# nrfModule.net
KiCad netlist of a schematic drawn in EAGLE
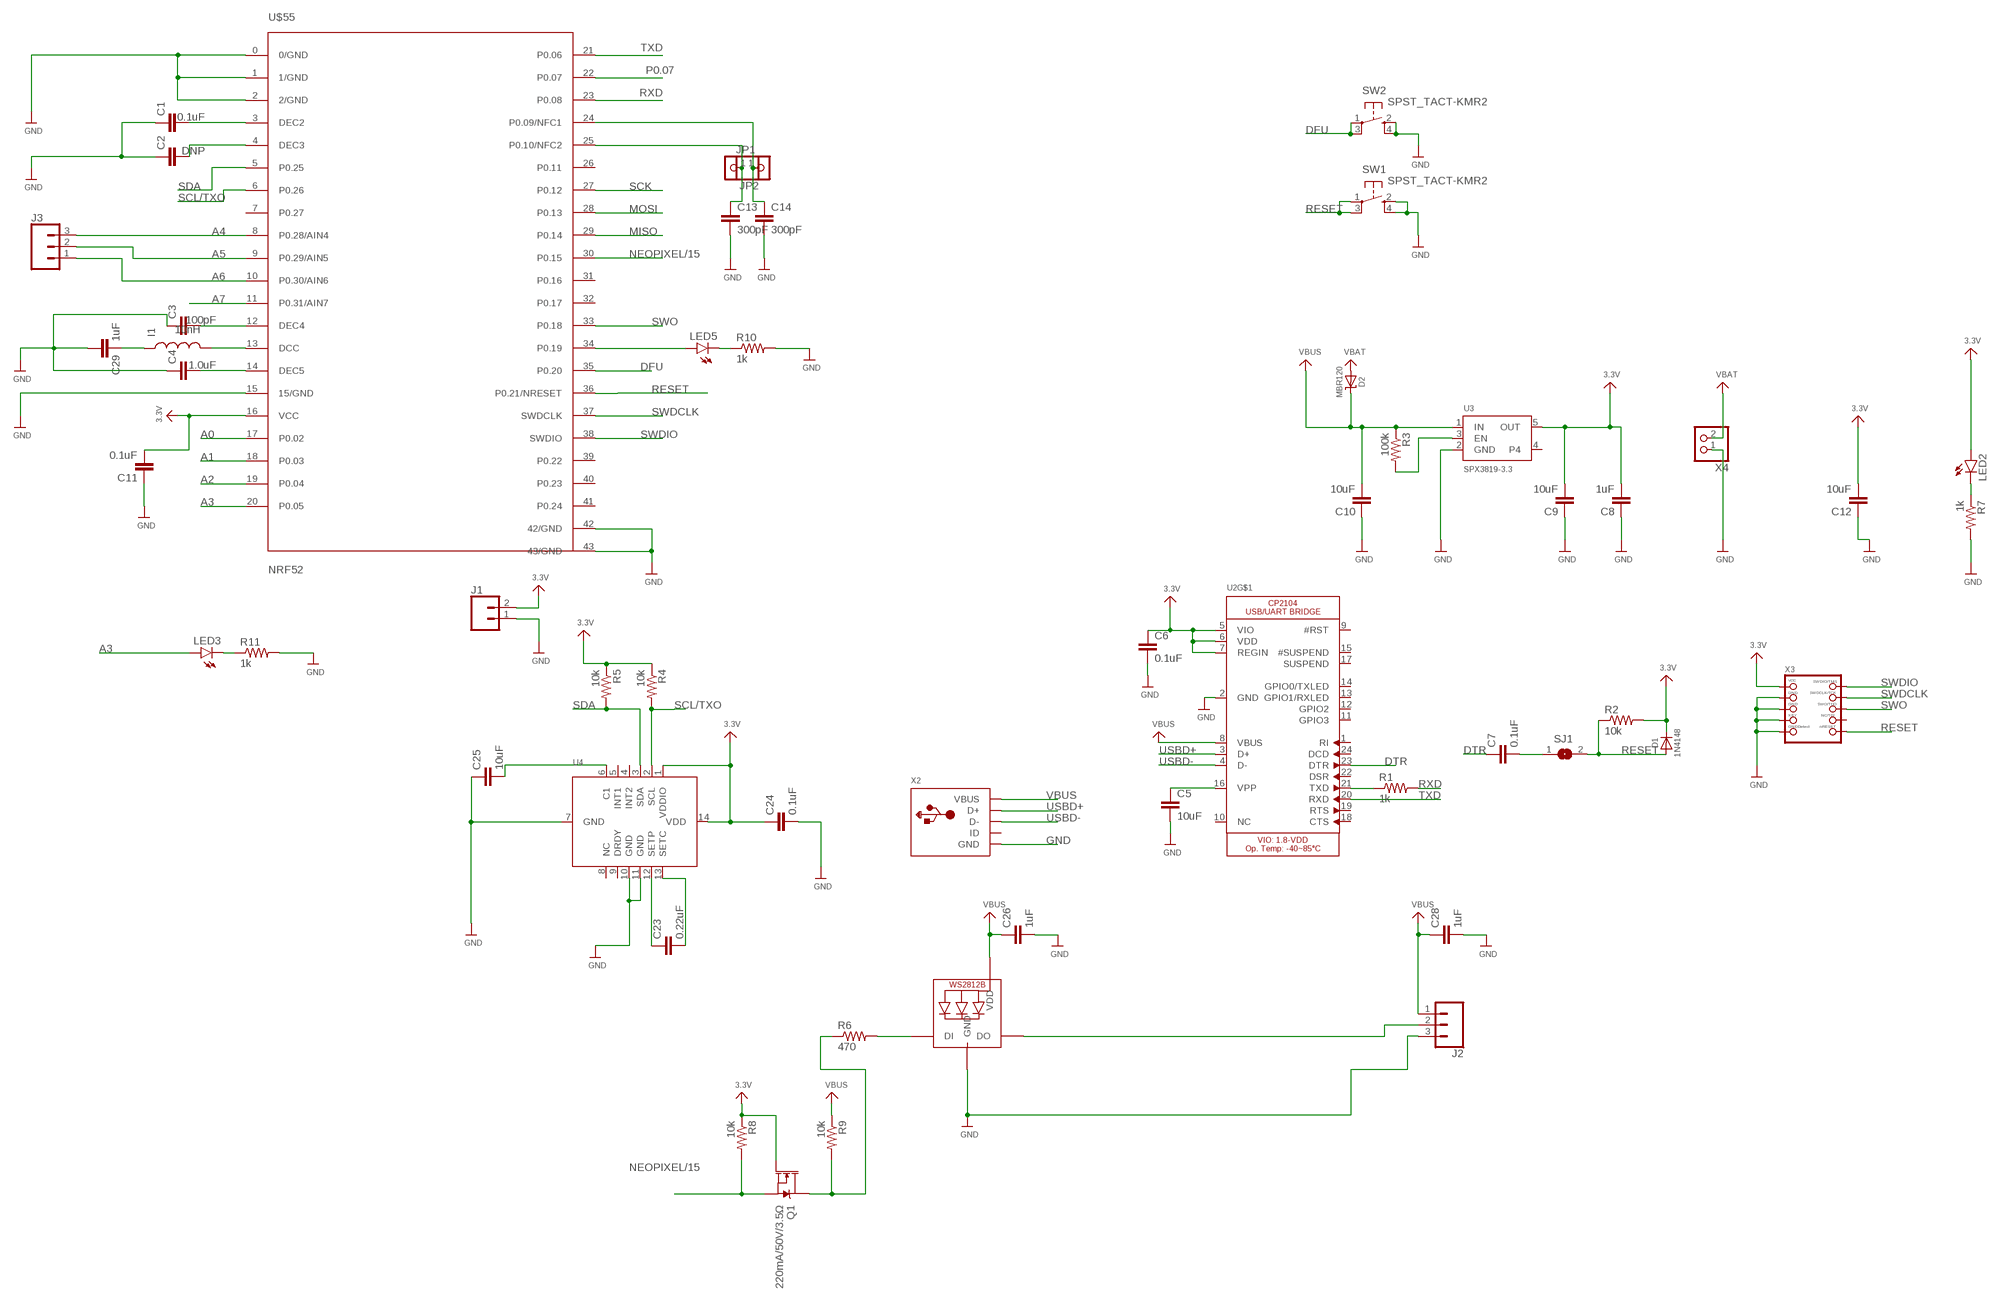
[diagram p0: schematic, sheet 1]

(export (version "E")
  (design (tool "Eeschema 10.0.6"))
  (components
    (comp (ref "C1")
      (value "0.1uF")
      (footprint "eagle-import:0805")
      (libsource (lib "eagle-import") (part "CAP"))
    )
    (comp (ref "C2")
      (value "DNP")
      (footprint "eagle-import:0805")
      (libsource (lib "eagle-import") (part "CAP"))
    )
    (comp (ref "C3")
      (value "100pF")
      (footprint "eagle-import:0805")
      (libsource (lib "eagle-import") (part "CAP"))
    )
    (comp (ref "C4")
      (value "1.0uF")
      (footprint "eagle-import:0805")
      (libsource (lib "eagle-import") (part "CAP"))
    )
    (comp (ref "C5")
      (value "10uF")
      (footprint "eagle-import:0805")
      (libsource (lib "eagle-import") (part "CAP"))
    )
    (comp (ref "C6")
      (value "0.1uF")
      (footprint "eagle-import:0805")
      (libsource (lib "eagle-import") (part "CAP"))
    )
    (comp (ref "C7")
      (value "0.1uF")
      (footprint "eagle-import:0805")
      (libsource (lib "eagle-import") (part "CAP"))
    )
    (comp (ref "C8")
      (value "1uF")
      (footprint "eagle-import:0805")
      (libsource (lib "eagle-import") (part "CAP"))
    )
    (comp (ref "C9")
      (value "10uF")
      (footprint "eagle-import:0805")
      (libsource (lib "eagle-import") (part "CAP"))
    )
    (comp (ref "C10")
      (value "10uF")
      (footprint "eagle-import:0805")
      (libsource (lib "eagle-import") (part "CAP"))
    )
    (comp (ref "C11")
      (value "0.1uF")
      (footprint "eagle-import:0805")
      (libsource (lib "eagle-import") (part "CAP"))
    )
    (comp (ref "C12")
      (value "10uF")
      (footprint "eagle-import:0805")
      (libsource (lib "eagle-import") (part "CAP"))
    )
    (comp (ref "C13")
      (value "300pF")
      (footprint "eagle-import:0805")
      (libsource (lib "eagle-import") (part "CAP"))
    )
    (comp (ref "C14")
      (value "300pF")
      (footprint "eagle-import:0805")
      (libsource (lib "eagle-import") (part "CAP"))
    )
    (comp (ref "C23")
      (value "0.22uF")
      (footprint "eagle-import:0805")
      (libsource (lib "eagle-import") (part "CAP"))
    )
    (comp (ref "C24")
      (value "0.1uF")
      (footprint "eagle-import:0805")
      (libsource (lib "eagle-import") (part "CAP"))
    )
    (comp (ref "C25")
      (value "10uF")
      (footprint "eagle-import:0805")
      (libsource (lib "eagle-import") (part "CAP"))
    )
    (comp (ref "C26")
      (value "1uF")
      (footprint "eagle-import:0805")
      (libsource (lib "eagle-import") (part "CAP"))
    )
    (comp (ref "C28")
      (value "1uF")
      (footprint "eagle-import:0805")
      (libsource (lib "eagle-import") (part "CAP"))
    )
    (comp (ref "C29")
      (value "1uF")
      (footprint "eagle-import:0805")
      (libsource (lib "eagle-import") (part "CAP"))
    )
    (comp (ref "D1")
      (value "1N4148")
      (footprint "eagle-import:SOD-323")
      (libsource (lib "eagle-import") (part "DIODESOD-323"))
    )
    (comp (ref "D2")
      (value "MBR120")
      (footprint "eagle-import:SOD-123")
      (libsource (lib "eagle-import") (part "DIODE-SCHOTTKYSOD-123"))
    )
    (comp (ref "I1")
      (value "10nH")
      (footprint "eagle-import:0805")
      (libsource (lib "eagle-import") (part "IND"))
    )
    (comp (ref "J1")
      (value "CONN_02")
      (footprint "eagle-import:1X02")
      (libsource (lib "eagle-import") (part "CONN_02"))
    )
    (comp (ref "J2")
      (value "CONN_03")
      (footprint "eagle-import:1X03")
      (libsource (lib "eagle-import") (part "CONN_03"))
    )
    (comp (ref "J3")
      (value "CONN_03")
      (footprint "eagle-import:1X03")
      (libsource (lib "eagle-import") (part "CONN_03"))
    )
    (comp (ref "JP1")
      (value "HEADER-1X12MM")
      (footprint "eagle-import:1X01_2MM")
      (libsource (lib "eagle-import") (part "HEADER-1X12MM"))
    )
    (comp (ref "JP2")
      (value "HEADER-1X12MM")
      (footprint "eagle-import:1X01_2MM")
      (libsource (lib "eagle-import") (part "HEADER-1X12MM"))
    )
    (comp (ref "LED1")
      (value "WS2812B5050")
      (footprint "eagle-import:WS2812B")
      (libsource (lib "eagle-import") (part "WS2812B5050"))
    )
    (comp (ref "LED2")
      (value "LED0603")
      (footprint "eagle-import:LED-0603")
      (libsource (lib "eagle-import") (part "LED0603"))
    )
    (comp (ref "LED3")
      (value "LED0603")
      (footprint "eagle-import:LED-0603")
      (libsource (lib "eagle-import") (part "LED0603"))
    )
    (comp (ref "LED5")
      (value "LED0603")
      (footprint "eagle-import:LED-0603")
      (libsource (lib "eagle-import") (part "LED0603"))
    )
    (comp (ref "Q1")
      (value "220mA/50V/3.5Ω")
      (footprint "eagle-import:SOT23-3")
      (libsource (lib "eagle-import") (part "MOSFET-NCH-BSS138"))
    )
    (comp (ref "R1")
      (value "1k")
      (footprint "eagle-import:0805")
      (libsource (lib "eagle-import") (part "RES"))
    )
    (comp (ref "R2")
      (value "10k")
      (footprint "eagle-import:0805")
      (libsource (lib "eagle-import") (part "RES"))
    )
    (comp (ref "R3")
      (value "100k")
      (footprint "eagle-import:0805")
      (libsource (lib "eagle-import") (part "RES"))
    )
    (comp (ref "R4")
      (value "10k")
      (footprint "eagle-import:0805")
      (libsource (lib "eagle-import") (part "RES"))
    )
    (comp (ref "R5")
      (value "10k")
      (footprint "eagle-import:0805")
      (libsource (lib "eagle-import") (part "RES"))
    )
    (comp (ref "R6")
      (value "470")
      (footprint "eagle-import:0805")
      (libsource (lib "eagle-import") (part "RES"))
    )
    (comp (ref "R7")
      (value "1k")
      (footprint "eagle-import:0805")
      (libsource (lib "eagle-import") (part "RES"))
    )
    (comp (ref "R8")
      (value "10k")
      (footprint "eagle-import:0805")
      (libsource (lib "eagle-import") (part "RES"))
    )
    (comp (ref "R9")
      (value "10k")
      (footprint "eagle-import:0805")
      (libsource (lib "eagle-import") (part "RES"))
    )
    (comp (ref "R10")
      (value "1k")
      (footprint "eagle-import:0805")
      (libsource (lib "eagle-import") (part "RES"))
    )
    (comp (ref "R11")
      (value "1k")
      (footprint "eagle-import:0805")
      (libsource (lib "eagle-import") (part "RES"))
    )
    (comp (ref "SJ1")
      (value "SOLDERJUMPERCLOSED")
      (footprint "eagle-import:SOLDERJUMPER_CLOSEDWIRE")
      (libsource (lib "eagle-import") (part "SOLDERJUMPERCLOSED"))
    )
    (comp (ref "SW1")
      (value "SPST_TACT-KMR2")
      (footprint "eagle-import:KMR2")
      (libsource (lib "eagle-import") (part "SPST_TACT-KMR2"))
    )
    (comp (ref "SW2")
      (value "SPST_TACT-KMR2")
      (footprint "eagle-import:KMR2")
      (libsource (lib "eagle-import") (part "SPST_TACT-KMR2"))
    )
    (comp (ref "U$55")
      (value "NRF52")
      (footprint "eagle-import:NRF52")
      (libsource (lib "eagle-import") (part "NRF52"))
    )
    (comp (ref "U2")
      (value "CP2104")
      (footprint "eagle-import:QFN24_4MM_SMSC")
      (libsource (lib "eagle-import") (part "CP2104"))
    )
    (comp (ref "U3")
      (value "SPX3819-3.3")
      (footprint "eagle-import:SOT23-5")
      (libsource (lib "eagle-import") (part "VREG_SOT23-5"))
    )
    (comp (ref "U4")
      (value "LSM303DLHC")
      (footprint "eagle-import:LGA14")
      (libsource (lib "eagle-import") (part "LSM303DLHC"))
    )
    (comp (ref "X2")
      (value "USB_MICRO_20329_V2")
      (footprint "eagle-import:4UCONN_20329_V2")
      (libsource (lib "eagle-import") (part "USB_MICRO_20329_V2"))
    )
    (comp (ref "X3")
      (value "JTAG-CORTEX")
      (footprint "eagle-import:2X05_1.27MM_SMT")
      (libsource (lib "eagle-import") (part "JTAG-CORTEX"))
    )
    (comp (ref "X4")
      (value "CON_JST_PH_2PIN")
      (footprint "eagle-import:JSTPH2")
      (libsource (lib "eagle-import") (part "CON_JST_PH_2PIN"))
    )
  )
  (nets
    (net (code "1") (name "/A0") (class "Default")
      (node (ref "U$55") (pin "17") (pinfunction "P0.02_17") (pintype "bidirectional"))
    )
    (net (code "2") (name "/A1") (class "Default")
      (node (ref "U$55") (pin "18") (pinfunction "P0.03_18") (pintype "bidirectional"))
    )
    (net (code "3") (name "/A2") (class "Default")
      (node (ref "U$55") (pin "19") (pinfunction "P0.04_19") (pintype "bidirectional"))
    )
    (net (code "4") (name "/A3") (class "Default")
      (node (ref "LED3") (pin "A") (pinfunction "A_A") (pintype "passive"))
      (node (ref "U$55") (pin "20") (pinfunction "P0.05_20") (pintype "bidirectional"))
    )
    (net (code "5") (name "/A4") (class "Default")
      (node (ref "J3") (pin "3") (pinfunction "3_3") (pintype "passive"))
      (node (ref "U$55") (pin "8") (pinfunction "P0.28/AIN4_8") (pintype "bidirectional"))
    )
    (net (code "6") (name "/A5") (class "Default")
      (node (ref "J3") (pin "2") (pinfunction "2_2") (pintype "passive"))
      (node (ref "U$55") (pin "9") (pinfunction "P0.29/AIN5_9") (pintype "bidirectional"))
    )
    (net (code "7") (name "/A6") (class "Default")
      (node (ref "J3") (pin "1") (pinfunction "1_1") (pintype "passive"))
      (node (ref "U$55") (pin "10") (pinfunction "P0.30/AIN6_10") (pintype "bidirectional"))
    )
    (net (code "8") (name "/A7") (class "Default")
      (node (ref "U$55") (pin "11") (pinfunction "P0.31/AIN7_11") (pintype "bidirectional"))
    )
    (net (code "9") (name "/DFU") (class "Default")
      (node (ref "SW2") (pin "1") (pinfunction "P_1") (pintype "passive"))
      (node (ref "SW2") (pin "3") (pinfunction "P1_3") (pintype "passive"))
      (node (ref "U$55") (pin "35") (pinfunction "P0.20_35") (pintype "bidirectional"))
    )
    (net (code "10") (name "/DTR") (class "Default")
      (node (ref "C7") (pin "1") (pinfunction "1_1") (pintype "passive"))
      (node (ref "U2") (pin "23") (pinfunction "DTR_23") (pintype "output"))
    )
    (net (code "11") (name "/MISO") (class "Default")
      (node (ref "U$55") (pin "29") (pinfunction "P0.14_29") (pintype "bidirectional"))
    )
    (net (code "12") (name "/MOSI") (class "Default")
      (node (ref "U$55") (pin "28") (pinfunction "P0.13_28") (pintype "bidirectional"))
    )
    (net (code "13") (name "/NEOPIXEL{slash}15") (class "Default")
      (node (ref "Q1") (pin "2") (pinfunction "S_2") (pintype "bidirectional"))
      (node (ref "R8") (pin "2") (pinfunction "2_2") (pintype "passive"))
      (node (ref "U$55") (pin "30") (pinfunction "P0.15_30") (pintype "bidirectional"))
    )
    (net (code "14") (name "/P0.07") (class "Default")
      (node (ref "U$55") (pin "22") (pinfunction "P0.07_22") (pintype "bidirectional"))
    )
    (net (code "15") (name "/RESET") (class "Default")
      (node (ref "D1") (pin "A") (pinfunction "A_A") (pintype "passive"))
      (node (ref "R2") (pin "1") (pinfunction "1_1") (pintype "passive"))
      (node (ref "SJ1") (pin "2") (pinfunction "2_2") (pintype "passive"))
      (node (ref "SW1") (pin "1") (pinfunction "P_1") (pintype "passive"))
      (node (ref "SW1") (pin "3") (pinfunction "P1_3") (pintype "passive"))
      (node (ref "U$55") (pin "36") (pinfunction "P0.21/NRESET_36") (pintype "bidirectional"))
      (node (ref "X3") (pin "10") (pinfunction "NRESET_10") (pintype "bidirectional"))
    )
    (net (code "16") (name "/RXD") (class "Default")
      (node (ref "R1") (pin "2") (pinfunction "2_2") (pintype "passive"))
      (node (ref "U$55") (pin "23") (pinfunction "P0.08_23") (pintype "bidirectional"))
    )
    (net (code "17") (name "/SCK") (class "Default")
      (node (ref "U$55") (pin "27") (pinfunction "P0.12_27") (pintype "bidirectional"))
    )
    (net (code "18") (name "/SCL{slash}TXO") (class "Default")
      (node (ref "R4") (pin "2") (pinfunction "2_2") (pintype "passive"))
      (node (ref "U$55") (pin "6") (pinfunction "P0.26_6") (pintype "bidirectional"))
      (node (ref "U4") (pin "2") (pinfunction "SCL_2") (pintype "bidirectional"))
    )
    (net (code "19") (name "/SDA") (class "Default")
      (node (ref "R5") (pin "2") (pinfunction "2_2") (pintype "passive"))
      (node (ref "U$55") (pin "5") (pinfunction "P0.25_5") (pintype "bidirectional"))
      (node (ref "U4") (pin "3") (pinfunction "SDA_3") (pintype "bidirectional"))
    )
    (net (code "20") (name "/SWDCLK") (class "Default")
      (node (ref "U$55") (pin "37") (pinfunction "SWDCLK_37") (pintype "bidirectional"))
      (node (ref "X3") (pin "4") (pinfunction "SWDCLK_4") (pintype "bidirectional"))
    )
    (net (code "21") (name "/SWDIO") (class "Default")
      (node (ref "U$55") (pin "38") (pinfunction "SWDIO_38") (pintype "bidirectional"))
      (node (ref "X3") (pin "2") (pinfunction "SWDIO_2") (pintype "bidirectional"))
    )
    (net (code "22") (name "/SWO") (class "Default")
      (node (ref "U$55") (pin "33") (pinfunction "P0.18_33") (pintype "bidirectional"))
      (node (ref "X3") (pin "6") (pinfunction "SWO_6") (pintype "bidirectional"))
    )
    (net (code "23") (name "/TXD") (class "Default")
      (node (ref "U$55") (pin "21") (pinfunction "P0.06_21") (pintype "bidirectional"))
      (node (ref "U2") (pin "20") (pinfunction "RXD_20") (pintype "input"))
    )
    (net (code "24") (name "/USBD+") (class "Default")
      (node (ref "U2") (pin "3") (pinfunction "D+_3") (pintype "bidirectional"))
      (node (ref "X2") (pin "D+") (pinfunction "D+_D+") (pintype "bidirectional"))
    )
    (net (code "25") (name "/USBD-") (class "Default")
      (node (ref "U2") (pin "4") (pinfunction "D-_4") (pintype "bidirectional"))
      (node (ref "X2") (pin "D-") (pinfunction "D-_D-") (pintype "bidirectional"))
    )
    (net (code "26") (name "3.3V") (class "Default")
      (node (ref "C11") (pin "2") (pinfunction "2_2") (pintype "passive"))
      (node (ref "C12") (pin "2") (pinfunction "2_2") (pintype "passive"))
      (node (ref "C24") (pin "1") (pinfunction "1_1") (pintype "passive"))
      (node (ref "C6") (pin "1") (pinfunction "1_1") (pintype "passive"))
      (node (ref "C8") (pin "2") (pinfunction "2_2") (pintype "passive"))
      (node (ref "C9") (pin "2") (pinfunction "2_2") (pintype "passive"))
      (node (ref "D1") (pin "C") (pinfunction "C_C") (pintype "passive"))
      (node (ref "J1") (pin "2") (pinfunction "2_2") (pintype "passive"))
      (node (ref "LED2") (pin "A") (pinfunction "A_A") (pintype "passive"))
      (node (ref "Q1") (pin "1") (pinfunction "G_1") (pintype "bidirectional"))
      (node (ref "R2") (pin "2") (pinfunction "2_2") (pintype "passive"))
      (node (ref "R4") (pin "1") (pinfunction "1_1") (pintype "passive"))
      (node (ref "R5") (pin "1") (pinfunction "1_1") (pintype "passive"))
      (node (ref "R8") (pin "1") (pinfunction "1_1") (pintype "passive"))
      (node (ref "U$55") (pin "16") (pinfunction "VCC_16") (pintype "bidirectional"))
      (node (ref "U2") (pin "5") (pinfunction "VIO_5") (pintype "power_in"))
      (node (ref "U2") (pin "6") (pinfunction "VDD_6") (pintype "power_in"))
      (node (ref "U2") (pin "7") (pinfunction "REGIN_7") (pintype "power_in"))
      (node (ref "U3") (pin "5") (pinfunction "OUT_5") (pintype "power_in"))
      (node (ref "U4") (pin "1") (pinfunction "VDDIO_1") (pintype "power_in"))
      (node (ref "U4") (pin "14") (pinfunction "VDD_14") (pintype "power_in"))
      (node (ref "X3") (pin "1") (pinfunction "VCC_1") (pintype "power_in"))
    )
    (net (code "27") (name "GND") (class "Default")
      (node (ref "C1") (pin "1") (pinfunction "1_1") (pintype "passive"))
      (node (ref "C10") (pin "1") (pinfunction "1_1") (pintype "passive"))
      (node (ref "C11") (pin "1") (pinfunction "1_1") (pintype "passive"))
      (node (ref "C12") (pin "1") (pinfunction "1_1") (pintype "passive"))
      (node (ref "C13") (pin "2") (pinfunction "2_2") (pintype "passive"))
      (node (ref "C14") (pin "2") (pinfunction "2_2") (pintype "passive"))
      (node (ref "C2") (pin "1") (pinfunction "1_1") (pintype "passive"))
      (node (ref "C24") (pin "2") (pinfunction "2_2") (pintype "passive"))
      (node (ref "C25") (pin "1") (pinfunction "1_1") (pintype "passive"))
      (node (ref "C26") (pin "2") (pinfunction "2_2") (pintype "passive"))
      (node (ref "C28") (pin "2") (pinfunction "2_2") (pintype "passive"))
      (node (ref "C29") (pin "2") (pinfunction "2_2") (pintype "passive"))
      (node (ref "C3") (pin "1") (pinfunction "1_1") (pintype "passive"))
      (node (ref "C4") (pin "1") (pinfunction "1_1") (pintype "passive"))
      (node (ref "C5") (pin "2") (pinfunction "2_2") (pintype "passive"))
      (node (ref "C6") (pin "2") (pinfunction "2_2") (pintype "passive"))
      (node (ref "C8") (pin "1") (pinfunction "1_1") (pintype "passive"))
      (node (ref "C9") (pin "1") (pinfunction "1_1") (pintype "passive"))
      (node (ref "J1") (pin "1") (pinfunction "1_1") (pintype "passive"))
      (node (ref "J2") (pin "3") (pinfunction "3_3") (pintype "passive"))
      (node (ref "LED1") (pin "3-GND") (pinfunction "GND_3-GND") (pintype "power_in"))
      (node (ref "R10") (pin "2") (pinfunction "2_2") (pintype "passive"))
      (node (ref "R11") (pin "2") (pinfunction "2_2") (pintype "passive"))
      (node (ref "R7") (pin "2") (pinfunction "2_2") (pintype "passive"))
      (node (ref "SW1") (pin "2") (pinfunction "S_2") (pintype "passive"))
      (node (ref "SW1") (pin "4") (pinfunction "S1_4") (pintype "passive"))
      (node (ref "SW2") (pin "2") (pinfunction "S_2") (pintype "passive"))
      (node (ref "SW2") (pin "4") (pinfunction "S1_4") (pintype "passive"))
      (node (ref "U$55") (pin "0") (pinfunction "0/GND_0") (pintype "bidirectional"))
      (node (ref "U$55") (pin "1") (pinfunction "1/GND_1") (pintype "bidirectional"))
      (node (ref "U$55") (pin "15") (pinfunction "15/GND_15") (pintype "bidirectional"))
      (node (ref "U$55") (pin "2") (pinfunction "2/GND_2") (pintype "bidirectional"))
      (node (ref "U$55") (pin "42") (pinfunction "42/GND_42") (pintype "bidirectional"))
      (node (ref "U$55") (pin "43") (pinfunction "43/GND_43") (pintype "bidirectional"))
      (node (ref "U2") (pin "2") (pinfunction "GND_2") (pintype "power_in"))
      (node (ref "U3") (pin "2") (pinfunction "GND_2") (pintype "power_in"))
      (node (ref "U4") (pin "10") (pinfunction "GND_10") (pintype "power_in"))
      (node (ref "U4") (pin "11") (pinfunction "GND_11") (pintype "power_in"))
      (node (ref "U4") (pin "7") (pinfunction "GND_7") (pintype "power_in"))
      (node (ref "X2") (pin "BASE@1") (pinfunction "GND_BASE@1") (pintype "power_in"))
      (node (ref "X2") (pin "BASE@2") (pinfunction "GND_BASE@2") (pintype "power_in"))
      (node (ref "X2") (pin "GND") (pinfunction "GND_GND") (pintype "power_in"))
      (node (ref "X2") (pin "SPRT@1") (pinfunction "GND_SPRT@1") (pintype "power_in"))
      (node (ref "X2") (pin "SPRT@2") (pinfunction "GND_SPRT@2") (pintype "power_in"))
      (node (ref "X2") (pin "SPRT@3") (pinfunction "GND_SPRT@3") (pintype "power_in"))
      (node (ref "X2") (pin "SPRT@4") (pinfunction "GND_SPRT@4") (pintype "power_in"))
      (node (ref "X3") (pin "3") (pinfunction "GND_3") (pintype "power_in"))
      (node (ref "X3") (pin "5") (pinfunction "GND_5") (pintype "power_in"))
      (node (ref "X3") (pin "7") (pinfunction "KEY_7") (pintype "bidirectional"))
      (node (ref "X3") (pin "9") (pinfunction "GNDDETECT_9") (pintype "bidirectional"))
      (node (ref "X4") (pin "1") (pinfunction "1_1") (pintype "passive"))
    )
    (net (code "28") (name "Net-(C7-Pad2)") (class "Default")
      (node (ref "C7") (pin "2") (pinfunction "2_2") (pintype "passive"))
      (node (ref "SJ1") (pin "1") (pinfunction "1_1") (pintype "passive"))
    )
    (net (code "29") (name "Net-(C29-Pad1)") (class "Default")
      (node (ref "C29") (pin "1") (pinfunction "1_1") (pintype "passive"))
      (node (ref "I1") (pin "1") (pinfunction "1_1") (pintype "passive"))
    )
    (net (code "30") (name "Net-(LED1-DI)") (class "Default")
      (node (ref "LED1") (pin "4-DIN") (pinfunction "DI_4-DIN") (pintype "input"))
      (node (ref "R6") (pin "2") (pinfunction "2_2") (pintype "passive"))
    )
    (net (code "31") (name "Net-(LED1-DO)") (class "Default")
      (node (ref "J2") (pin "2") (pinfunction "2_2") (pintype "passive"))
      (node (ref "LED1") (pin "2-DOUT") (pinfunction "DO_2-DOUT") (pintype "output"))
    )
    (net (code "32") (name "Net-(LED2-PadC)") (class "Default")
      (node (ref "LED2") (pin "C") (pinfunction "C_C") (pintype "passive"))
      (node (ref "R7") (pin "1") (pinfunction "1_1") (pintype "passive"))
    )
    (net (code "33") (name "Net-(LED3-PadC)") (class "Default")
      (node (ref "LED3") (pin "C") (pinfunction "C_C") (pintype "passive"))
      (node (ref "R11") (pin "1") (pinfunction "1_1") (pintype "passive"))
    )
    (net (code "34") (name "Net-(LED5-PadC)") (class "Default")
      (node (ref "LED5") (pin "C") (pinfunction "C_C") (pintype "passive"))
      (node (ref "R10") (pin "1") (pinfunction "1_1") (pintype "passive"))
    )
    (net (code "35") (name "Net-(Q1-D)") (class "Default")
      (node (ref "Q1") (pin "3") (pinfunction "D_3") (pintype "bidirectional"))
      (node (ref "R6") (pin "1") (pinfunction "1_1") (pintype "passive"))
      (node (ref "R9") (pin "2") (pinfunction "2_2") (pintype "passive"))
    )
    (net (code "36") (name "Net-(U$55-DCC)") (class "Default")
      (node (ref "I1") (pin "2") (pinfunction "2_2") (pintype "passive"))
      (node (ref "U$55") (pin "13") (pinfunction "DCC_13") (pintype "bidirectional"))
    )
    (net (code "37") (name "Net-(U$55-DEC2)") (class "Default")
      (node (ref "C1") (pin "2") (pinfunction "2_2") (pintype "passive"))
      (node (ref "U$55") (pin "3") (pinfunction "DEC2_3") (pintype "bidirectional"))
    )
    (net (code "38") (name "Net-(U$55-DEC3)") (class "Default")
      (node (ref "C2") (pin "2") (pinfunction "2_2") (pintype "passive"))
      (node (ref "U$55") (pin "4") (pinfunction "DEC3_4") (pintype "bidirectional"))
    )
    (net (code "39") (name "Net-(U$55-DEC4)") (class "Default")
      (node (ref "C3") (pin "2") (pinfunction "2_2") (pintype "passive"))
      (node (ref "U$55") (pin "12") (pinfunction "DEC4_12") (pintype "bidirectional"))
    )
    (net (code "40") (name "Net-(U$55-DEC5)") (class "Default")
      (node (ref "C4") (pin "2") (pinfunction "2_2") (pintype "passive"))
      (node (ref "U$55") (pin "14") (pinfunction "DEC5_14") (pintype "bidirectional"))
    )
    (net (code "41") (name "Net-(U$55-P0.09{slash}NFC1)") (class "Default")
      (node (ref "C14") (pin "1") (pinfunction "1_1") (pintype "passive"))
      (node (ref "JP1") (pin "1") (pinfunction "1_1") (pintype "passive"))
      (node (ref "U$55") (pin "24") (pinfunction "P0.09/NFC1_24") (pintype "bidirectional"))
    )
    (net (code "42") (name "Net-(U$55-P0.10{slash}NFC2)") (class "Default")
      (node (ref "C13") (pin "1") (pinfunction "1_1") (pintype "passive"))
      (node (ref "JP2") (pin "1") (pinfunction "1_1") (pintype "passive"))
      (node (ref "U$55") (pin "25") (pinfunction "P0.10/NFC2_25") (pintype "bidirectional"))
    )
    (net (code "43") (name "Net-(U$55-P0.19)") (class "Default")
      (node (ref "LED5") (pin "A") (pinfunction "A_A") (pintype "passive"))
      (node (ref "U$55") (pin "34") (pinfunction "P0.19_34") (pintype "bidirectional"))
    )
    (net (code "44") (name "Net-(U2A-TXD)") (class "Default")
      (node (ref "R1") (pin "1") (pinfunction "1_1") (pintype "passive"))
      (node (ref "U2") (pin "21") (pinfunction "TXD_21") (pintype "output"))
    )
    (net (code "45") (name "Net-(U2A-VPP)") (class "Default")
      (node (ref "C5") (pin "1") (pinfunction "1_1") (pintype "passive"))
      (node (ref "U2") (pin "16") (pinfunction "VPP_16") (pintype "bidirectional"))
    )
    (net (code "46") (name "Net-(U3-EN)") (class "Default")
      (node (ref "R3") (pin "2") (pinfunction "2_2") (pintype "passive"))
      (node (ref "U3") (pin "3") (pinfunction "EN_3") (pintype "input"))
    )
    (net (code "47") (name "Net-(U4-C1)") (class "Default")
      (node (ref "C25") (pin "2") (pinfunction "2_2") (pintype "passive"))
      (node (ref "U4") (pin "6") (pinfunction "C1_6") (pintype "bidirectional"))
    )
    (net (code "48") (name "Net-(U4-SETC)") (class "Default")
      (node (ref "C23") (pin "2") (pinfunction "2_2") (pintype "passive"))
      (node (ref "U4") (pin "13") (pinfunction "SETC_13") (pintype "bidirectional"))
    )
    (net (code "49") (name "Net-(U4-SETP)") (class "Default")
      (node (ref "C23") (pin "1") (pinfunction "1_1") (pintype "passive"))
      (node (ref "U4") (pin "12") (pinfunction "SETP_12") (pintype "bidirectional"))
    )
    (net (code "50") (name "VBAT") (class "Default")
      (node (ref "D2") (pin "A") (pinfunction "A_A") (pintype "passive"))
      (node (ref "X4") (pin "2") (pinfunction "2_2") (pintype "passive"))
    )
    (net (code "51") (name "VBUS") (class "Default")
      (node (ref "C10") (pin "2") (pinfunction "2_2") (pintype "passive"))
      (node (ref "C26") (pin "1") (pinfunction "1_1") (pintype "passive"))
      (node (ref "C28") (pin "1") (pinfunction "1_1") (pintype "passive"))
      (node (ref "D2") (pin "C") (pinfunction "C_C") (pintype "passive"))
      (node (ref "J2") (pin "1") (pinfunction "1_1") (pintype "passive"))
      (node (ref "LED1") (pin "1-VDD") (pinfunction "VDD_1-VDD") (pintype "power_in"))
      (node (ref "R3") (pin "1") (pinfunction "1_1") (pintype "passive"))
      (node (ref "R9") (pin "1") (pinfunction "1_1") (pintype "passive"))
      (node (ref "U2") (pin "8") (pinfunction "VBUS_8") (pintype "power_in"))
      (node (ref "U3") (pin "1") (pinfunction "IN_1") (pintype "power_in"))
      (node (ref "X2") (pin "VBUS") (pinfunction "VBUS_VBUS") (pintype "power_in"))
    )
    (net (code "52") (name "unconnected-(U$55-P0.11-Pad26)") (class "Default")
      (node (ref "U$55") (pin "26") (pinfunction "P0.11_26") (pintype "bidirectional"))
    )
    (net (code "53") (name "unconnected-(U$55-P0.16-Pad31)") (class "Default")
      (node (ref "U$55") (pin "31") (pinfunction "P0.16_31") (pintype "bidirectional"))
    )
    (net (code "54") (name "unconnected-(U$55-P0.17-Pad32)") (class "Default")
      (node (ref "U$55") (pin "32") (pinfunction "P0.17_32") (pintype "bidirectional"))
    )
    (net (code "55") (name "unconnected-(U$55-P0.22-Pad39)") (class "Default")
      (node (ref "U$55") (pin "39") (pinfunction "P0.22_39") (pintype "bidirectional"))
    )
    (net (code "56") (name "unconnected-(U$55-P0.23-Pad40)") (class "Default")
      (node (ref "U$55") (pin "40") (pinfunction "P0.23_40") (pintype "bidirectional"))
    )
    (net (code "57") (name "unconnected-(U$55-P0.24-Pad41)") (class "Default")
      (node (ref "U$55") (pin "41") (pinfunction "P0.24_41") (pintype "bidirectional"))
    )
    (net (code "58") (name "unconnected-(U$55-P0.27-Pad7)") (class "Default")
      (node (ref "U$55") (pin "7") (pinfunction "P0.27_7") (pintype "bidirectional"))
    )
    (net (code "59") (name "unconnected-(U2A-#RST-Pad9)") (class "Default")
      (node (ref "U2") (pin "9") (pinfunction "#RST_9") (pintype "bidirectional"))
    )
    (net (code "60") (name "unconnected-(U2A-#SUSPEND-Pad15)") (class "Default")
      (node (ref "U2") (pin "15") (pinfunction "#SUSPEND_15") (pintype "output"))
    )
    (net (code "61") (name "unconnected-(U2A-CTS-Pad18)") (class "Default")
      (node (ref "U2") (pin "18") (pinfunction "CTS_18") (pintype "input"))
    )
    (net (code "62") (name "unconnected-(U2A-DCD-Pad24)") (class "Default")
      (node (ref "U2") (pin "24") (pinfunction "DCD_24") (pintype "input"))
    )
    (net (code "63") (name "unconnected-(U2A-DSR-Pad22)") (class "Default")
      (node (ref "U2") (pin "22") (pinfunction "DSR_22") (pintype "input"))
    )
    (net (code "64") (name "unconnected-(U2A-GPIO0{slash}TXLED-Pad14)") (class "Default")
      (node (ref "U2") (pin "14") (pinfunction "GPIO0/TXLED_14") (pintype "bidirectional"))
    )
    (net (code "65") (name "unconnected-(U2A-GPIO1{slash}RXLED-Pad13)") (class "Default")
      (node (ref "U2") (pin "13") (pinfunction "GPIO1/RXLED_13") (pintype "bidirectional"))
    )
    (net (code "66") (name "unconnected-(U2A-GPIO2-Pad12)") (class "Default")
      (node (ref "U2") (pin "12") (pinfunction "GPIO2_12") (pintype "bidirectional"))
    )
    (net (code "67") (name "unconnected-(U2A-GPIO3-Pad11)") (class "Default")
      (node (ref "U2") (pin "11") (pinfunction "GPIO3_11") (pintype "bidirectional"))
    )
    (net (code "68") (name "unconnected-(U2A-NC-Pad10)") (class "Default")
      (node (ref "U2") (pin "10") (pinfunction "NC_10") (pintype "no_connect"))
    )
    (net (code "69") (name "unconnected-(U2A-RI-Pad1)") (class "Default")
      (node (ref "U2") (pin "1") (pinfunction "RI_1") (pintype "input"))
    )
    (net (code "70") (name "unconnected-(U2A-RTS-Pad19)") (class "Default")
      (node (ref "U2") (pin "19") (pinfunction "RTS_19") (pintype "output"))
    )
    (net (code "71") (name "unconnected-(U2A-SUSPEND-Pad17)") (class "Default")
      (node (ref "U2") (pin "17") (pinfunction "SUSPEND_17") (pintype "output"))
    )
    (net (code "72") (name "unconnected-(U3-P4-Pad4)") (class "Default")
      (node (ref "U3") (pin "4") (pinfunction "P4_4") (pintype "bidirectional"))
    )
    (net (code "73") (name "unconnected-(U4-DRDY-Pad9)") (class "Default")
      (node (ref "U4") (pin "9") (pinfunction "DRDY_9") (pintype "output"))
    )
    (net (code "74") (name "unconnected-(U4-INT1-Pad5)") (class "Default")
      (node (ref "U4") (pin "5") (pinfunction "INT1_5") (pintype "output"))
    )
    (net (code "75") (name "unconnected-(U4-INT2-Pad4)") (class "Default")
      (node (ref "U4") (pin "4") (pinfunction "INT2_4") (pintype "output"))
    )
    (net (code "76") (name "unconnected-(U4-NC-Pad8)") (class "Default")
      (node (ref "U4") (pin "8") (pinfunction "NC_8") (pintype "bidirectional"))
    )
    (net (code "77") (name "unconnected-(X2-PadID)") (class "Default")
      (node (ref "X2") (pin "ID") (pinfunction "ID_ID") (pintype "bidirectional"))
    )
    (net (code "78") (name "unconnected-(X3-TDI-Pad8)") (class "Default")
      (node (ref "X3") (pin "8") (pinfunction "TDI_8") (pintype "bidirectional"))
    )
  )
)
